# WifiNode_Pwr_R00.net
KiCad netlist of a schematic drawn in Altium Designer
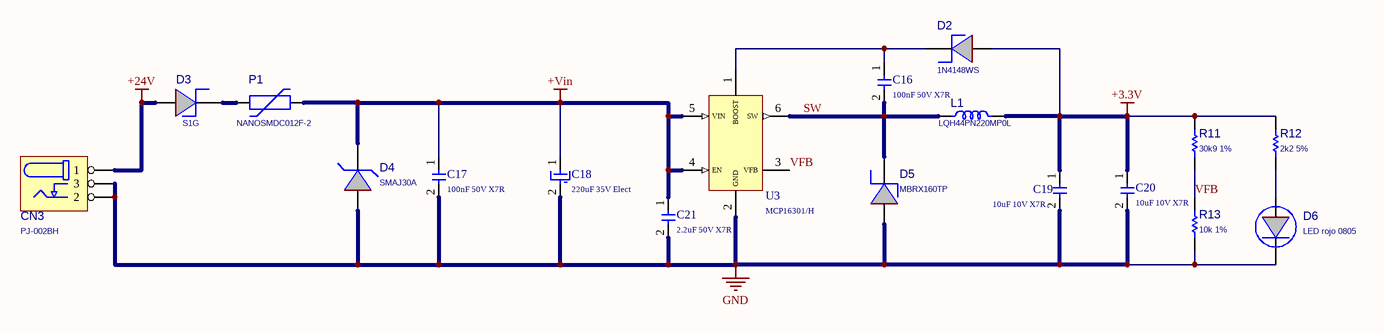
[diagram p0: WifiNode_Pwr_R00.SchDoc]

(export (version "E")
  (design (tool "Eeschema 10.0.6"))
  (components
    (comp (ref "C16")
      (value "100nF 50V X7R")
      (footprint "C_0805")
      (description "Not polarized capacitor")
      (libsource (lib "IDCI_TP1_SFARA") (part "CAP_NP"))
    )
    (comp (ref "C17")
      (value "100nF 50V X7R")
      (footprint "C_0805")
      (description "Not polarized capacitor")
      (libsource (lib "IDCI_TP1_SFARA") (part "CAP_NP"))
    )
    (comp (ref "C18")
      (value "220uF 35V Elect")
      (footprint "C_RAD_0.135_H_8X12_S")
      (description "Polarized capacitor")
      (libsource (lib "IDCI_TP1_SFARA") (part "CAP_P"))
    )
    (comp (ref "C19")
      (value "10uF 10V X7R")
      (footprint "C_0805")
      (description "Not polarized capacitor")
      (libsource (lib "IDCI_TP1_SFARA") (part "CAP_NP"))
    )
    (comp (ref "C20")
      (value "10uF 10V X7R")
      (footprint "C_0805")
      (description "Not polarized capacitor")
      (libsource (lib "IDCI_TP1_SFARA") (part "CAP_NP"))
    )
    (comp (ref "C21")
      (value "2.2uF 50V X7R")
      (footprint "C_1206")
      (description "Not polarized capacitor")
      (libsource (lib "IDCI_TP1_SFARA") (part "CAP_NP"))
    )
    (comp (ref "CN3")
      (value "PJ-002BH")
      (footprint "PJ002B")
      (description "Barrel Power Connector")
      (libsource (lib "IDCI_TP1_SFARA") (part "CN_PowerJack"))
    )
    (comp (ref "D2")
      (value "1N4148WS")
      (footprint "D_0805")
      (description "Diode Shottky")
      (libsource (lib "IDCI_TP1_SFARA") (part "DIODO_SH"))
    )
    (comp (ref "D3")
      (value "S1G")
      (footprint "D_SMA")
      (description "Diode Shottky")
      (libsource (lib "") (part "DIODO_SH_1"))
    )
    (comp (ref "D4")
      (value "SMAJ30A")
      (footprint "D_SMA")
      (description "Unidirectional TVS")
      (libsource (lib "IDCI_TP1_SFARA") (part "DIODE_TVS_1"))
    )
    (comp (ref "D5")
      (value "MBRX160TP")
      (footprint "SOD_123")
      (description "Diode Shottky")
      (libsource (lib "IDCI_TP1_SFARA") (part "DIODO_SH"))
    )
    (comp (ref "D6")
      (value "LED rojo 0805")
      (footprint "D_0805")
      (description "LED")
      (libsource (lib "IDCI_TP1_SFARA") (part "LED_1"))
    )
    (comp (ref "L1")
      (value "LQH44PN220MP0L")
      (footprint "LQH44")
      (description "Inductor")
      (libsource (lib "IDCI_TP1_SFARA") (part "IND"))
    )
    (comp (ref "P1")
      (value "NANOSMDC012F-2")
      (footprint "NANOSMDC")
      (description "Polyswitch")
      (libsource (lib "IDCI_TP1_SFARA") (part "PLYSW"))
    )
    (comp (ref "R11")
      (value "30k9 1%")
      (footprint "R_0805")
      (description "Resistor")
      (libsource (lib "IDCI_TP1_SFARA") (part "Res1"))
    )
    (comp (ref "R12")
      (value "2k2 5%")
      (footprint "R_0805")
      (description "Resistor")
      (libsource (lib "IDCI_TP1_SFARA") (part "Res1"))
    )
    (comp (ref "R13")
      (value "10k 1%")
      (footprint "R_0805")
      (description "Resistor")
      (libsource (lib "IDCI_TP1_SFARA") (part "Res1"))
    )
    (comp (ref "U3")
      (value "MCP16301/H")
      (footprint "SOT23-6")
      (libsource (lib "IDCI_TP1_SFARA") (part "MCP16301/H"))
    )
  )
  (nets
    (net (code "1") (name "+3.3V") (class "Default")
      (node (ref "C19") (pin "1") (pintype "passive"))
      (node (ref "C20") (pin "1") (pintype "passive"))
      (node (ref "D2") (pin "1") (pinfunction "A_1") (pintype "passive"))
      (node (ref "L1") (pin "2") (pinfunction "2_2") (pintype "passive"))
      (node (ref "R11") (pin "2") (pinfunction "2_2") (pintype "passive"))
      (node (ref "R12") (pin "2") (pinfunction "2_2") (pintype "passive"))
    )
    (net (code "2") (name "+24V") (class "Default")
      (node (ref "CN3") (pin "1") (pinfunction "1_1") (pintype "passive"))
      (node (ref "D3") (pin "1") (pinfunction "A_1") (pintype "passive"))
    )
    (net (code "3") (name "+Vin") (class "Default")
      (node (ref "C17") (pin "1") (pintype "passive"))
      (node (ref "C18") (pin "1") (pintype "passive"))
      (node (ref "C21") (pin "1") (pintype "passive"))
      (node (ref "D4") (pin "2") (pinfunction "K_2") (pintype "passive"))
      (node (ref "P1") (pin "2") (pinfunction "2_2") (pintype "passive"))
      (node (ref "U3") (pin "4") (pinfunction "EN_4") (pintype "input"))
      (node (ref "U3") (pin "5") (pinfunction "VIN_5") (pintype "input"))
    )
    (net (code "4") (name "/SW") (class "Default")
      (node (ref "C16") (pin "2") (pintype "passive"))
      (node (ref "D5") (pin "2") (pinfunction "K_2") (pintype "passive"))
      (node (ref "L1") (pin "1") (pinfunction "1_1") (pintype "passive"))
      (node (ref "U3") (pin "6") (pinfunction "SW_6") (pintype "output"))
    )
    (net (code "5") (name "/VFB") (class "Default")
      (node (ref "R11") (pin "1") (pinfunction "1_1") (pintype "passive"))
      (node (ref "R13") (pin "2") (pinfunction "2_2") (pintype "passive"))
      (node (ref "U3") (pin "3") (pinfunction "VFB_3") (pintype "passive"))
    )
    (net (code "6") (name "GND") (class "Default")
      (node (ref "C17") (pin "2") (pintype "passive"))
      (node (ref "C18") (pin "2") (pintype "passive"))
      (node (ref "C19") (pin "2") (pintype "passive"))
      (node (ref "C20") (pin "2") (pintype "passive"))
      (node (ref "C21") (pin "2") (pintype "passive"))
      (node (ref "CN3") (pin "2") (pinfunction "2_2") (pintype "passive"))
      (node (ref "CN3") (pin "3") (pinfunction "3_3") (pintype "passive"))
      (node (ref "D4") (pin "1") (pinfunction "A_1") (pintype "passive"))
      (node (ref "D5") (pin "1") (pinfunction "A_1") (pintype "passive"))
      (node (ref "D6") (pin "2") (pinfunction "K_2") (pintype "passive"))
      (node (ref "R13") (pin "1") (pinfunction "1_1") (pintype "passive"))
      (node (ref "U3") (pin "2") (pinfunction "GND_2") (pintype "passive"))
    )
    (net (code "7") (name "Net-(D2-K)") (class "Default")
      (node (ref "C16") (pin "1") (pintype "passive"))
      (node (ref "D2") (pin "2") (pinfunction "K_2") (pintype "passive"))
      (node (ref "U3") (pin "1") (pinfunction "BOOST_1") (pintype "passive"))
    )
    (net (code "8") (name "Net-(D3-K)") (class "Default")
      (node (ref "D3") (pin "2") (pinfunction "K_2") (pintype "passive"))
      (node (ref "P1") (pin "1") (pinfunction "1_1") (pintype "passive"))
    )
    (net (code "9") (name "Net-(D6-A)") (class "Default")
      (node (ref "D6") (pin "1") (pinfunction "A_1") (pintype "passive"))
      (node (ref "R12") (pin "1") (pinfunction "1_1") (pintype "passive"))
    )
  )
)
